# 10_VO_Interface_2.net
KiCad netlist of a schematic drawn in Altium Designer
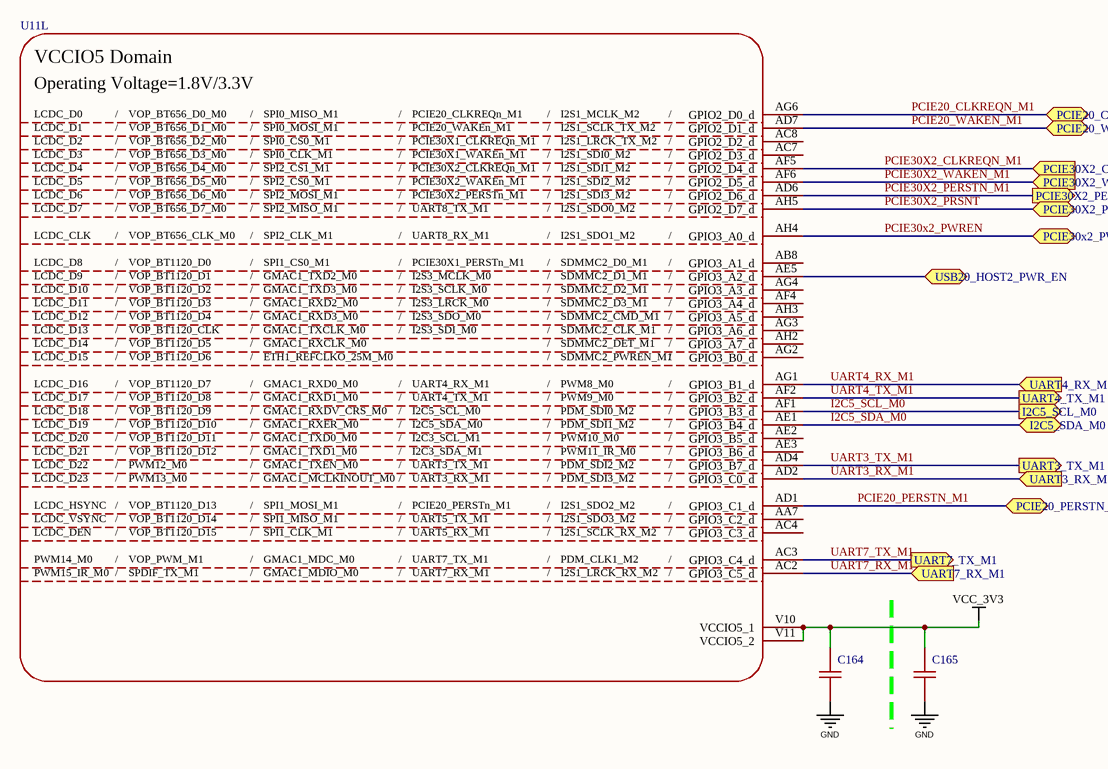
[diagram p0: 10_VO Interface_2.schdoc]

(export (version "E")
  (design (tool "Eeschema 10.0.6"))
  (components
    (comp (ref "C164")
      (value "100nF")
      (footprint "C0201")
      (description "容值:100nF;精度:±10%;额定电压:16V;材质(温度系数):X5R;")
      (fields
        (field (name "MANUFACTURER") "SAMSUNG(三星)")
        (field (name "MANUFACTURER PART") "CL03A104KO3NNNC")
      )
      (libsource (lib "altium-import") (part "root_0_CL03A104KO3NNNC_"))
    )
    (comp (ref "C165")
      (value "1uF")
      (footprint "C0402")
      (description "容值:1uF;精度:±10%;额定电压:25V;材质(温度系数):X5R;")
      (fields
        (field (name "MANUFACTURER") "SAMSUNG(三星)")
        (field (name "MANUFACTURER PART") "CL05A105KA5NQNC")
      )
      (libsource (lib "altium-import") (part "root_1_CL05A105KA5NQNC_"))
    )
    (comp (ref "U11")
      (value "SOC_RK3568")
      (footprint "RK3568")
      (fields (field (name "MANUFACTURER") "Rockchip (瑞芯微)") (field (name "CREATED BY") "JJJ"))
      (libsource (lib "altium-import") (part "root_0_SOC_RK3568_"))
    )
  )
  (nets
    (net (code "1") (name "/I2C5_SCL_M0") (class "Default")
      (node (ref "U11") (pin "AF1") (pinfunction "GPIO3_B3_d_AF1") (pintype "passive"))
    )
    (net (code "2") (name "/I2C5_SDA_M0") (class "Default")
      (node (ref "U11") (pin "AE1") (pinfunction "GPIO3_B4_d_AE1") (pintype "passive"))
    )
    (net (code "3") (name "/PCIE20_CLKREQN_M1") (class "Default")
      (node (ref "U11") (pin "AG6") (pinfunction "GPIO2_D0_d_AG6") (pintype "passive"))
    )
    (net (code "4") (name "/PCIE20_PERSTN_M1") (class "Default")
      (node (ref "U11") (pin "AD1") (pinfunction "GPIO3_C1_d_AD1") (pintype "passive"))
    )
    (net (code "5") (name "/PCIE20_WAKEN_M1") (class "Default")
      (node (ref "U11") (pin "AD7") (pinfunction "GPIO2_D1_d_AD7") (pintype "passive"))
    )
    (net (code "6") (name "/PCIE30X2_CLKREQN_M1") (class "Default")
      (node (ref "U11") (pin "AF5") (pinfunction "GPIO2_D4_d_AF5") (pintype "passive"))
    )
    (net (code "7") (name "/PCIE30X2_PERSTN_M1") (class "Default")
      (node (ref "U11") (pin "AD6") (pinfunction "GPIO2_D6_d_AD6") (pintype "passive"))
    )
    (net (code "8") (name "/PCIE30X2_PRSNT") (class "Default")
      (node (ref "U11") (pin "AH5") (pinfunction "GPIO2_D7_d_AH5") (pintype "passive"))
    )
    (net (code "9") (name "/PCIE30X2_WAKEN_M1") (class "Default")
      (node (ref "U11") (pin "AF6") (pinfunction "GPIO2_D5_d_AF6") (pintype "passive"))
    )
    (net (code "10") (name "/PCIE30x2_PWREN") (class "Default")
      (node (ref "U11") (pin "AH4") (pinfunction "GPIO3_A0_d_AH4") (pintype "passive"))
    )
    (net (code "11") (name "/UART3_RX_M1") (class "Default")
      (node (ref "U11") (pin "AD2") (pinfunction "GPIO3_C0_d_AD2") (pintype "passive"))
    )
    (net (code "12") (name "/UART3_TX_M1") (class "Default")
      (node (ref "U11") (pin "AD4") (pinfunction "GPIO3_B7_d_AD4") (pintype "passive"))
    )
    (net (code "13") (name "/UART4_RX_M1") (class "Default")
      (node (ref "U11") (pin "AG1") (pinfunction "GPIO3_B1_d_AG1") (pintype "passive"))
    )
    (net (code "14") (name "/UART4_TX_M1") (class "Default")
      (node (ref "U11") (pin "AF2") (pinfunction "GPIO3_B2_d_AF2") (pintype "passive"))
    )
    (net (code "15") (name "/UART7_RX_M1") (class "Default")
      (node (ref "U11") (pin "AC2") (pinfunction "GPIO3_C5_d_AC2") (pintype "passive"))
    )
    (net (code "16") (name "/UART7_TX_M1") (class "Default")
      (node (ref "U11") (pin "AC3") (pinfunction "GPIO3_C4_d_AC3") (pintype "passive"))
    )
    (net (code "17") (name "/USB20_HOST2_PWR_EN") (class "Default")
      (node (ref "U11") (pin "AE5") (pinfunction "GPIO3_A2_d_AE5") (pintype "passive"))
    )
    (net (code "18") (name "GND") (class "Default")
      (node (ref "C164") (pin "1") (pinfunction "1_1") (pintype "passive"))
      (node (ref "C165") (pin "1") (pinfunction "1_1") (pintype "passive"))
    )
    (net (code "19") (name "VCC_3V3") (class "Default")
      (node (ref "C164") (pin "2") (pinfunction "2_2") (pintype "passive"))
      (node (ref "C165") (pin "2") (pinfunction "2_2") (pintype "passive"))
      (node (ref "U11") (pin "V10") (pinfunction "VCCIO5_1_V10") (pintype "passive"))
      (node (ref "U11") (pin "V11") (pinfunction "VCCIO5_2_V11") (pintype "passive"))
    )
    (net (code "20") (name "unconnected-(U11L-GPIO2_D2_d-PadAC8)") (class "Default")
      (node (ref "U11") (pin "AC8") (pinfunction "GPIO2_D2_d_AC8") (pintype "passive"))
    )
    (net (code "21") (name "unconnected-(U11L-GPIO2_D3_d-PadAC7)") (class "Default")
      (node (ref "U11") (pin "AC7") (pinfunction "GPIO2_D3_d_AC7") (pintype "passive"))
    )
    (net (code "22") (name "unconnected-(U11L-GPIO3_A1_d-PadAB8)") (class "Default")
      (node (ref "U11") (pin "AB8") (pinfunction "GPIO3_A1_d_AB8") (pintype "passive"))
    )
    (net (code "23") (name "unconnected-(U11L-GPIO3_A3_d-PadAG4)") (class "Default")
      (node (ref "U11") (pin "AG4") (pinfunction "GPIO3_A3_d_AG4") (pintype "passive"))
    )
    (net (code "24") (name "unconnected-(U11L-GPIO3_A4_d-PadAF4)") (class "Default")
      (node (ref "U11") (pin "AF4") (pinfunction "GPIO3_A4_d_AF4") (pintype "passive"))
    )
    (net (code "25") (name "unconnected-(U11L-GPIO3_A5_d-PadAH3)") (class "Default")
      (node (ref "U11") (pin "AH3") (pinfunction "GPIO3_A5_d_AH3") (pintype "passive"))
    )
    (net (code "26") (name "unconnected-(U11L-GPIO3_A6_d-PadAG3)") (class "Default")
      (node (ref "U11") (pin "AG3") (pinfunction "GPIO3_A6_d_AG3") (pintype "passive"))
    )
    (net (code "27") (name "unconnected-(U11L-GPIO3_A7_d-PadAH2)") (class "Default")
      (node (ref "U11") (pin "AH2") (pinfunction "GPIO3_A7_d_AH2") (pintype "passive"))
    )
    (net (code "28") (name "unconnected-(U11L-GPIO3_B0_d-PadAG2)") (class "Default")
      (node (ref "U11") (pin "AG2") (pinfunction "GPIO3_B0_d_AG2") (pintype "passive"))
    )
    (net (code "29") (name "unconnected-(U11L-GPIO3_B5_d-PadAE2)") (class "Default")
      (node (ref "U11") (pin "AE2") (pinfunction "GPIO3_B5_d_AE2") (pintype "passive"))
    )
    (net (code "30") (name "unconnected-(U11L-GPIO3_B6_d-PadAE3)") (class "Default")
      (node (ref "U11") (pin "AE3") (pinfunction "GPIO3_B6_d_AE3") (pintype "passive"))
    )
    (net (code "31") (name "unconnected-(U11L-GPIO3_C2_d-PadAA7)") (class "Default")
      (node (ref "U11") (pin "AA7") (pinfunction "GPIO3_C2_d_AA7") (pintype "passive"))
    )
    (net (code "32") (name "unconnected-(U11L-GPIO3_C3_d-PadAC4)") (class "Default")
      (node (ref "U11") (pin "AC4") (pinfunction "GPIO3_C3_d_AC4") (pintype "passive"))
    )
  )
)
